# Sheet2.net
KiCad netlist of a schematic drawn in Altium Designer
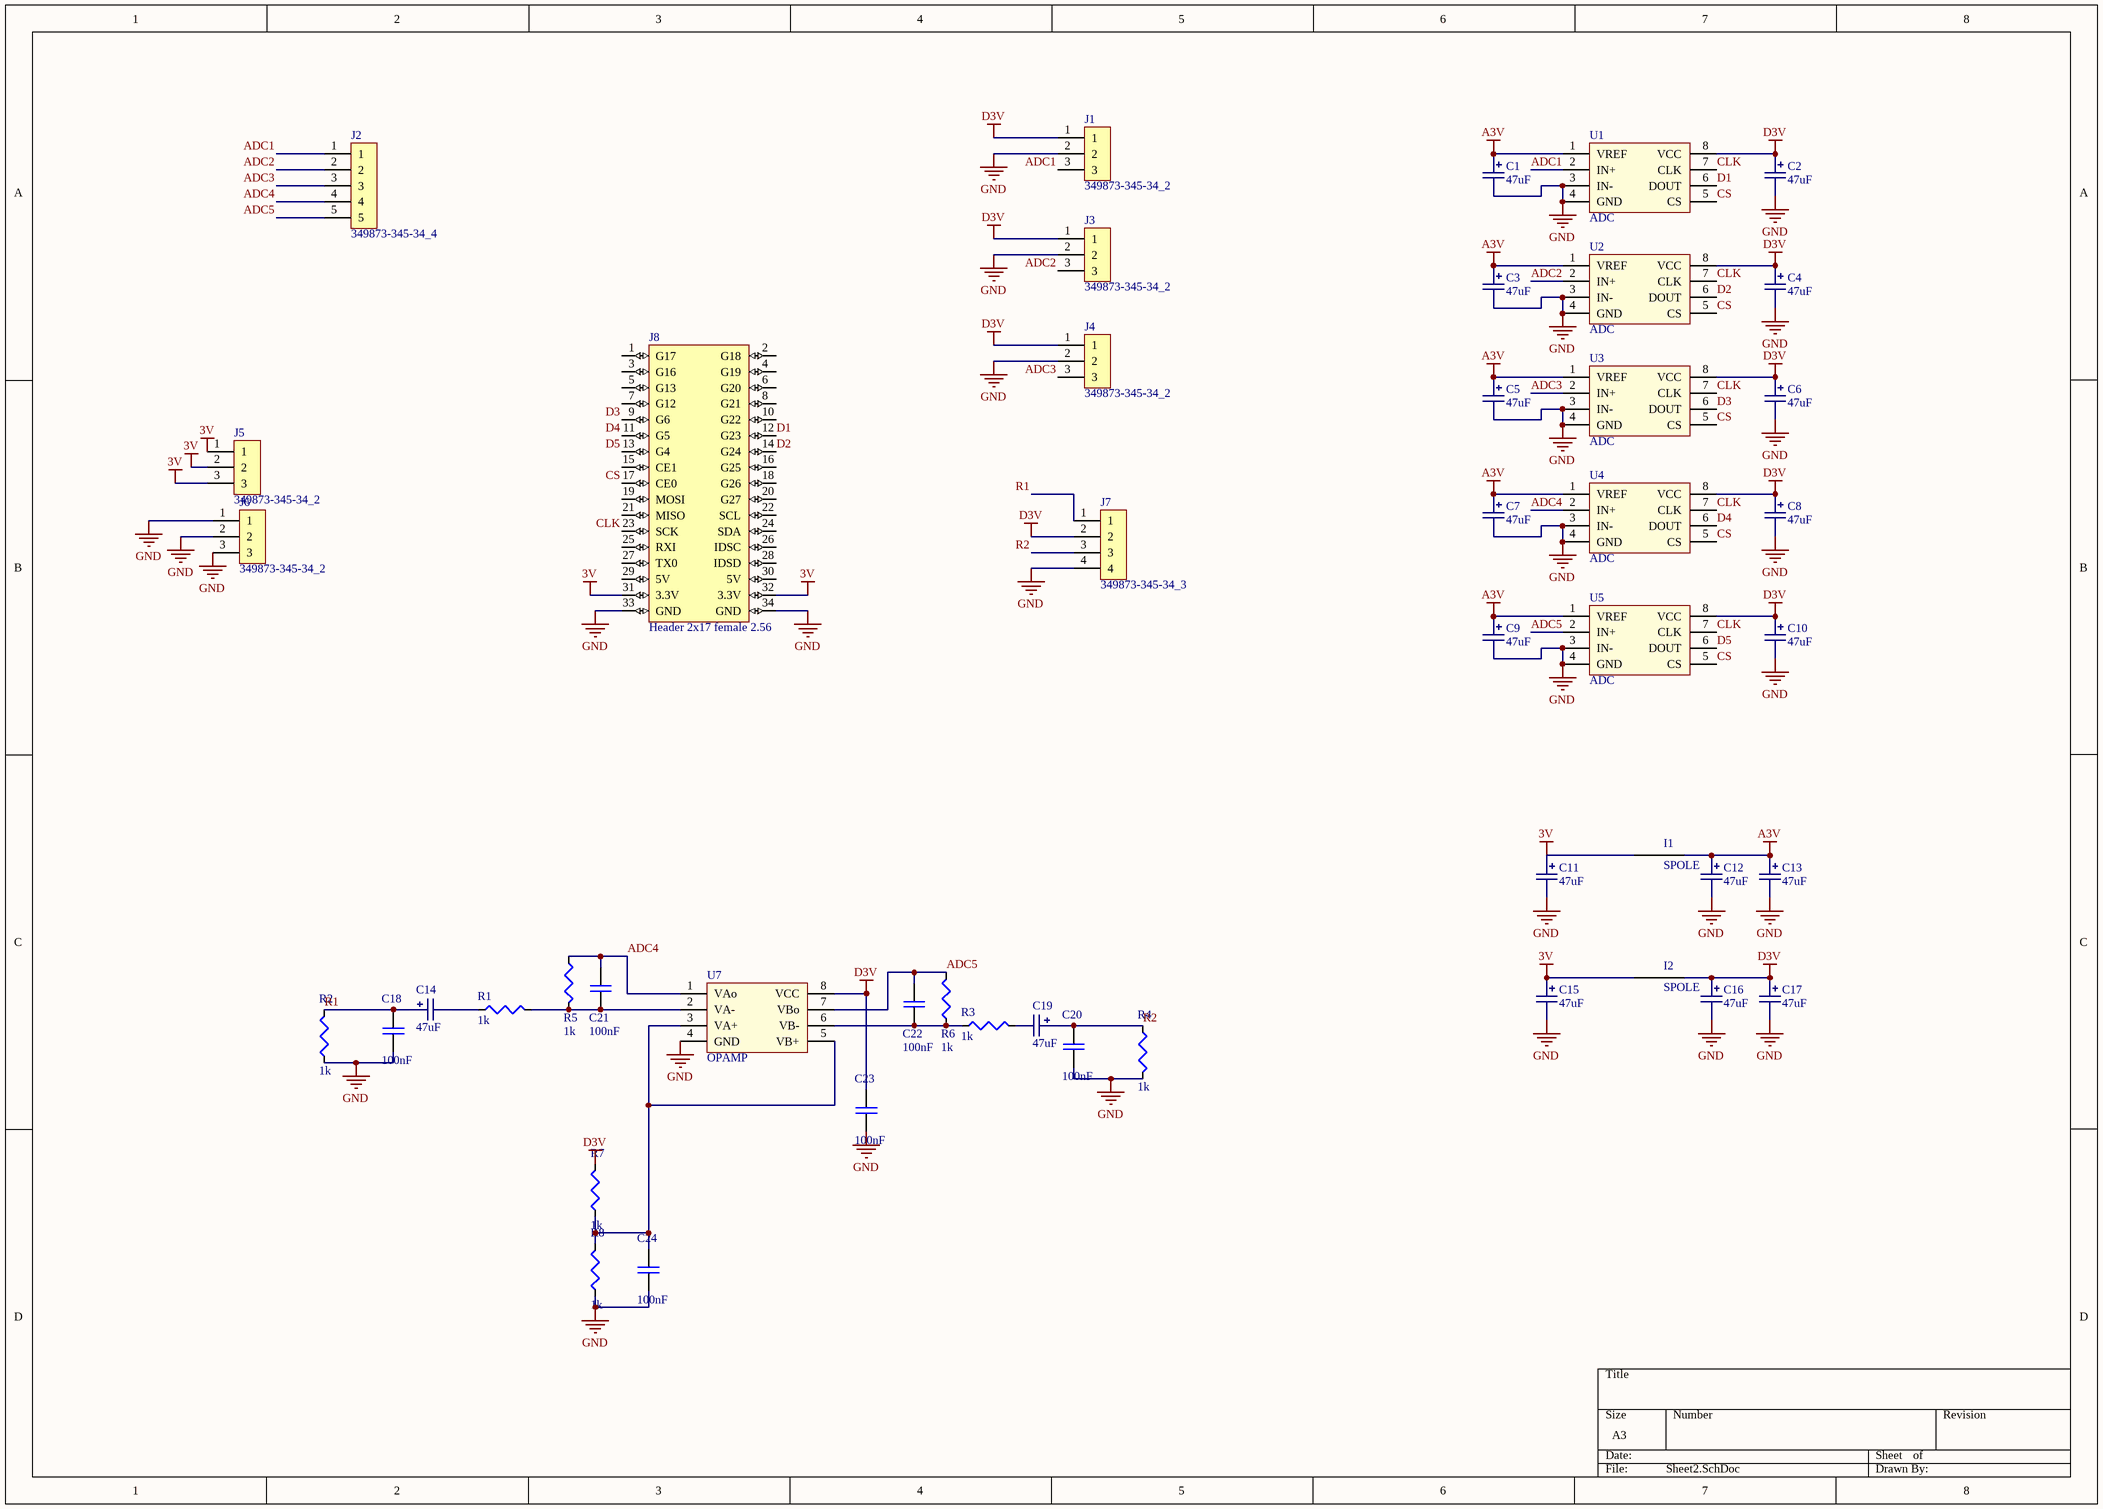
[diagram p0: Sheet2.SchDoc]

(export (version "E")
  (design (tool "Eeschema 10.0.6"))
  (components
    (comp (ref "C1")
      (value "47uF")
      (footprint "CAPPR20D05H11")
      (description "25V, Elektrolytt")
      (libsource (lib "OVLib_64") (part "POLCAP"))
    )
    (comp (ref "C2")
      (value "47uF")
      (footprint "CAPPR20D05H11")
      (description "25V, Elektrolytt")
      (libsource (lib "OVLib_64") (part "POLCAP"))
    )
    (comp (ref "C3")
      (value "47uF")
      (footprint "CAPPR20D05H11")
      (description "25V, Elektrolytt")
      (libsource (lib "OVLib_64") (part "POLCAP"))
    )
    (comp (ref "C4")
      (value "47uF")
      (footprint "CAPPR20D05H11")
      (description "25V, Elektrolytt")
      (libsource (lib "OVLib_64") (part "POLCAP"))
    )
    (comp (ref "C5")
      (value "47uF")
      (footprint "CAPPR20D05H11")
      (description "25V, Elektrolytt")
      (libsource (lib "OVLib_64") (part "POLCAP"))
    )
    (comp (ref "C6")
      (value "47uF")
      (footprint "CAPPR20D05H11")
      (description "25V, Elektrolytt")
      (libsource (lib "OVLib_64") (part "POLCAP"))
    )
    (comp (ref "C7")
      (value "47uF")
      (footprint "CAPPR20D05H11")
      (description "25V, Elektrolytt")
      (libsource (lib "OVLib_64") (part "POLCAP"))
    )
    (comp (ref "C8")
      (value "47uF")
      (footprint "CAPPR20D05H11")
      (description "25V, Elektrolytt")
      (libsource (lib "OVLib_64") (part "POLCAP"))
    )
    (comp (ref "C9")
      (value "47uF")
      (footprint "CAPPR20D05H11")
      (description "25V, Elektrolytt")
      (libsource (lib "OVLib_64") (part "POLCAP"))
    )
    (comp (ref "C10")
      (value "47uF")
      (footprint "CAPPR20D05H11")
      (description "25V, Elektrolytt")
      (libsource (lib "OVLib_64") (part "POLCAP"))
    )
    (comp (ref "C11")
      (value "47uF")
      (footprint "CAPPR20D05H11")
      (description "25V, Elektrolytt")
      (libsource (lib "OVLib_64") (part "POLCAP"))
    )
    (comp (ref "C12")
      (value "47uF")
      (footprint "CAPPR20D05H11")
      (description "25V, Elektrolytt")
      (libsource (lib "OVLib_64") (part "POLCAP"))
    )
    (comp (ref "C13")
      (value "47uF")
      (footprint "CAPPR20D05H11")
      (description "25V, Elektrolytt")
      (libsource (lib "OVLib_64") (part "POLCAP"))
    )
    (comp (ref "C14")
      (value "47uF")
      (footprint "CAPPR20D05H11")
      (description "25V, Elektrolytt")
      (libsource (lib "OVLib_64") (part "POLCAP"))
    )
    (comp (ref "C15")
      (value "47uF")
      (footprint "CAPPR20D05H11")
      (description "25V, Elektrolytt")
      (libsource (lib "OVLib_64") (part "POLCAP"))
    )
    (comp (ref "C16")
      (value "47uF")
      (footprint "CAPPR20D05H11")
      (description "25V, Elektrolytt")
      (libsource (lib "OVLib_64") (part "POLCAP"))
    )
    (comp (ref "C17")
      (value "47uF")
      (footprint "CAPPR20D05H11")
      (description "25V, Elektrolytt")
      (libsource (lib "OVLib_64") (part "POLCAP"))
    )
    (comp (ref "C18")
      (value "100nF")
      (footprint "C0805")
      (description "C0805")
      (fields (field (name "Comment") "08053C105KAT2A"))
      (libsource (lib "Passive components") (part "08053C105KAT2A"))
    )
    (comp (ref "C19")
      (value "47uF")
      (footprint "CAPPR20D05H11")
      (description "25V, Elektrolytt")
      (libsource (lib "OVLib_64") (part "POLCAP"))
    )
    (comp (ref "C20")
      (value "100nF")
      (footprint "C0805")
      (description "C0805")
      (fields (field (name "Comment") "08053C105KAT2A"))
      (libsource (lib "Passive components") (part "08053C105KAT2A"))
    )
    (comp (ref "C21")
      (value "100nF")
      (footprint "C0805")
      (description "C0805")
      (fields (field (name "Comment") "08053C105KAT2A"))
      (libsource (lib "Passive components") (part "08053C105KAT2A"))
    )
    (comp (ref "C22")
      (value "100nF")
      (footprint "C0805")
      (description "C0805")
      (fields (field (name "Comment") "08053C105KAT2A"))
      (libsource (lib "Passive components") (part "08053C105KAT2A"))
    )
    (comp (ref "C23")
      (value "100nF")
      (footprint "C0805")
      (description "C0805")
      (fields (field (name "Comment") "08053C105KAT2A"))
      (libsource (lib "Passive components") (part "08053C105KAT2A"))
    )
    (comp (ref "C24")
      (value "100nF")
      (footprint "C0805")
      (description "C0805")
      (fields (field (name "Comment") "08053C105KAT2A"))
      (libsource (lib "Passive components") (part "08053C105KAT2A"))
    )
    (comp (ref "I1")
      (value "SPOLE")
      (footprint "Microcontrollers:PCBComponent_1")
      (libsource (lib "Passive components") (part "SPOLE"))
    )
    (comp (ref "I2")
      (value "SPOLE")
      (footprint "Microcontrollers:PCBComponent_1")
      (libsource (lib "Passive components") (part "SPOLE"))
    )
    (comp (ref "J1")
      (value "349873-345-34_2")
      (footprint "Header 1x3 male")
      (description "Header 1x3 male 2.54mm")
      (libsource (lib "Connectors") (part "349873-345-34_2"))
    )
    (comp (ref "J2")
      (value "349873-345-34_4")
      (footprint "Header 1x5 male")
      (description "Header 1x5 male 2.54mm")
      (libsource (lib "Connectors") (part "349873-345-34_4"))
    )
    (comp (ref "J3")
      (value "349873-345-34_2")
      (footprint "Header 1x3 male")
      (description "Header 1x3 male 2.54mm")
      (libsource (lib "Connectors") (part "349873-345-34_2"))
    )
    (comp (ref "J4")
      (value "349873-345-34_2")
      (footprint "Header 1x3 male")
      (description "Header 1x3 male 2.54mm")
      (libsource (lib "Connectors") (part "349873-345-34_2"))
    )
    (comp (ref "J5")
      (value "349873-345-34_2")
      (footprint "Header 1x3 male")
      (description "Header 1x3 male 2.54mm")
      (libsource (lib "Connectors") (part "349873-345-34_2"))
    )
    (comp (ref "J6")
      (value "349873-345-34_2")
      (footprint "Header 1x3 male")
      (description "Header 1x3 male 2.54mm")
      (libsource (lib "Connectors") (part "349873-345-34_2"))
    )
    (comp (ref "J7")
      (value "349873-345-34_3")
      (footprint "Header 1x4 male")
      (description "Header 1x4 male 2.54mm")
      (libsource (lib "Connectors") (part "349873-345-34_3"))
    )
    (comp (ref "J8")
      (value "Header 2x17 female 2.56")
      (footprint "Header 2x17 female 2.56")
      (libsource (lib "Connectors") (part "Header 2x17 female 2.56"))
    )
    (comp (ref "R1")
      (value "1k")
      (footprint "R0805")
      (description "R0805")
      (fields (field (name "Comment") "CRCW08050000Z0EA"))
      (libsource (lib "Passive components") (part "CRCW08050000Z0EA"))
    )
    (comp (ref "R2")
      (value "1k")
      (footprint "R0805")
      (description "R0805")
      (fields (field (name "Comment") "CRCW08050000Z0EA"))
      (libsource (lib "Passive components") (part "CRCW08050000Z0EA"))
    )
    (comp (ref "R3")
      (value "1k")
      (footprint "R0805")
      (description "R0805")
      (fields (field (name "Comment") "CRCW08050000Z0EA"))
      (libsource (lib "Passive components") (part "CRCW08050000Z0EA"))
    )
    (comp (ref "R4")
      (value "1k")
      (footprint "R0805")
      (description "R0805")
      (fields (field (name "Comment") "CRCW08050000Z0EA"))
      (libsource (lib "Passive components") (part "CRCW08050000Z0EA"))
    )
    (comp (ref "R5")
      (value "1k")
      (footprint "R0805")
      (description "R0805")
      (fields (field (name "Comment") "CRCW08050000Z0EA"))
      (libsource (lib "Passive components") (part "CRCW08050000Z0EA"))
    )
    (comp (ref "R6")
      (value "1k")
      (footprint "R0805")
      (description "R0805")
      (fields (field (name "Comment") "CRCW08050000Z0EA"))
      (libsource (lib "Passive components") (part "CRCW08050000Z0EA"))
    )
    (comp (ref "R7")
      (value "1k")
      (footprint "R0805")
      (description "R0805")
      (fields (field (name "Comment") "CRCW08050000Z0EA"))
      (libsource (lib "Passive components") (part "CRCW08050000Z0EA"))
    )
    (comp (ref "R8")
      (value "1k")
      (footprint "R0805")
      (description "R0805")
      (fields (field (name "Comment") "CRCW08050000Z0EA"))
      (libsource (lib "Passive components") (part "CRCW08050000Z0EA"))
    )
    (comp (ref "U1") (value "ADC") (footprint "SOKKEL8") (libsource (lib "Microcontrollers") (part "ADC")))
    (comp (ref "U2") (value "ADC") (footprint "SOKKEL8") (libsource (lib "Microcontrollers") (part "ADC")))
    (comp (ref "U3") (value "ADC") (footprint "SOKKEL8") (libsource (lib "Microcontrollers") (part "ADC")))
    (comp (ref "U4") (value "ADC") (footprint "SOKKEL8") (libsource (lib "Microcontrollers") (part "ADC")))
    (comp (ref "U5") (value "ADC") (footprint "SOKKEL8") (libsource (lib "Microcontrollers") (part "ADC")))
    (comp (ref "U7")
      (value "OPAMP")
      (footprint "Microcontrollers:SOKKEL8")
      (libsource (lib "Microcontrollers") (part "OPAMP"))
    )
  )
  (nets
    (net (code "1") (name "/ADC1") (class "Default")
      (node (ref "J1") (pin "3") (pinfunction "3_3") (pintype "passive"))
      (node (ref "J2") (pin "1") (pinfunction "1_1") (pintype "passive"))
      (node (ref "U1") (pin "2") (pinfunction "IN+_2") (pintype "power_in"))
    )
    (net (code "2") (name "/ADC2") (class "Default")
      (node (ref "J2") (pin "2") (pinfunction "2_2") (pintype "passive"))
      (node (ref "J3") (pin "3") (pinfunction "3_3") (pintype "passive"))
      (node (ref "U2") (pin "2") (pinfunction "IN+_2") (pintype "power_in"))
    )
    (net (code "3") (name "/ADC3") (class "Default")
      (node (ref "J2") (pin "3") (pinfunction "3_3") (pintype "passive"))
      (node (ref "J4") (pin "3") (pinfunction "3_3") (pintype "passive"))
      (node (ref "U3") (pin "2") (pinfunction "IN+_2") (pintype "power_in"))
    )
    (net (code "4") (name "/ADC4") (class "Default")
      (node (ref "C21") (pin "1") (pinfunction "1_1") (pintype "passive"))
      (node (ref "J2") (pin "4") (pinfunction "4_4") (pintype "passive"))
      (node (ref "R5") (pin "1") (pinfunction "1_1") (pintype "passive"))
      (node (ref "U4") (pin "2") (pinfunction "IN+_2") (pintype "power_in"))
      (node (ref "U7") (pin "1") (pinfunction "VAo_1") (pintype "power_in"))
    )
    (net (code "5") (name "/ADC5") (class "Default")
      (node (ref "C22") (pin "1") (pinfunction "1_1") (pintype "passive"))
      (node (ref "J2") (pin "5") (pinfunction "5_5") (pintype "passive"))
      (node (ref "R6") (pin "1") (pinfunction "1_1") (pintype "passive"))
      (node (ref "U5") (pin "2") (pinfunction "IN+_2") (pintype "power_in"))
      (node (ref "U7") (pin "7") (pinfunction "VBo_7") (pintype "power_in"))
    )
    (net (code "6") (name "/CLK") (class "Default")
      (node (ref "J8") (pin "23") (pinfunction "SCK_23") (pintype "bidirectional"))
      (node (ref "U1") (pin "7") (pinfunction "CLK_7") (pintype "power_in"))
      (node (ref "U2") (pin "7") (pinfunction "CLK_7") (pintype "power_in"))
      (node (ref "U3") (pin "7") (pinfunction "CLK_7") (pintype "power_in"))
      (node (ref "U4") (pin "7") (pinfunction "CLK_7") (pintype "power_in"))
      (node (ref "U5") (pin "7") (pinfunction "CLK_7") (pintype "power_in"))
    )
    (net (code "7") (name "/CS") (class "Default")
      (node (ref "J8") (pin "17") (pinfunction "CE0_17") (pintype "bidirectional"))
      (node (ref "U1") (pin "5") (pinfunction "CS_5") (pintype "power_in"))
      (node (ref "U2") (pin "5") (pinfunction "CS_5") (pintype "power_in"))
      (node (ref "U3") (pin "5") (pinfunction "CS_5") (pintype "power_in"))
      (node (ref "U4") (pin "5") (pinfunction "CS_5") (pintype "power_in"))
      (node (ref "U5") (pin "5") (pinfunction "CS_5") (pintype "power_in"))
    )
    (net (code "8") (name "/D1") (class "Default")
      (node (ref "J8") (pin "12") (pinfunction "G23_12") (pintype "bidirectional"))
      (node (ref "U1") (pin "6") (pinfunction "DOUT_6") (pintype "power_in"))
    )
    (net (code "9") (name "/D2") (class "Default")
      (node (ref "J8") (pin "14") (pinfunction "G24_14") (pintype "bidirectional"))
      (node (ref "U2") (pin "6") (pinfunction "DOUT_6") (pintype "power_in"))
    )
    (net (code "10") (name "/D3") (class "Default")
      (node (ref "J8") (pin "9") (pinfunction "G6_9") (pintype "bidirectional"))
      (node (ref "U3") (pin "6") (pinfunction "DOUT_6") (pintype "power_in"))
    )
    (net (code "11") (name "/D4") (class "Default")
      (node (ref "J8") (pin "11") (pinfunction "G5_11") (pintype "bidirectional"))
      (node (ref "U4") (pin "6") (pinfunction "DOUT_6") (pintype "power_in"))
    )
    (net (code "12") (name "/D5") (class "Default")
      (node (ref "J8") (pin "13") (pinfunction "G4_13") (pintype "bidirectional"))
      (node (ref "U5") (pin "6") (pinfunction "DOUT_6") (pintype "power_in"))
    )
    (net (code "13") (name "/R1") (class "Default")
      (node (ref "C14") (pin "2") (pinfunction "2_2") (pintype "passive"))
      (node (ref "C18") (pin "2") (pinfunction "2_2") (pintype "passive"))
      (node (ref "J7") (pin "1") (pinfunction "1_1") (pintype "passive"))
      (node (ref "R2") (pin "2") (pinfunction "2_2") (pintype "passive"))
    )
    (net (code "14") (name "/R2") (class "Default")
      (node (ref "C19") (pin "2") (pinfunction "2_2") (pintype "passive"))
      (node (ref "C20") (pin "2") (pinfunction "2_2") (pintype "passive"))
      (node (ref "J7") (pin "3") (pinfunction "3_3") (pintype "passive"))
      (node (ref "R4") (pin "2") (pinfunction "2_2") (pintype "passive"))
    )
    (net (code "15") (name "3V") (class "Default")
      (node (ref "C11") (pin "2") (pinfunction "2_2") (pintype "passive"))
      (node (ref "C15") (pin "2") (pinfunction "2_2") (pintype "passive"))
      (node (ref "I1") (pin "1") (pinfunction "1_1") (pintype "power_in"))
      (node (ref "I2") (pin "1") (pinfunction "1_1") (pintype "power_in"))
      (node (ref "J5") (pin "1") (pinfunction "1_1") (pintype "passive"))
      (node (ref "J5") (pin "2") (pinfunction "2_2") (pintype "passive"))
      (node (ref "J5") (pin "3") (pinfunction "3_3") (pintype "passive"))
      (node (ref "J8") (pin "31") (pinfunction "3.3V_31") (pintype "bidirectional"))
      (node (ref "J8") (pin "32") (pinfunction "3.3V_32") (pintype "bidirectional"))
    )
    (net (code "16") (name "A3V") (class "Default")
      (node (ref "C1") (pin "2") (pinfunction "2_2") (pintype "passive"))
      (node (ref "C12") (pin "2") (pinfunction "2_2") (pintype "passive"))
      (node (ref "C13") (pin "2") (pinfunction "2_2") (pintype "passive"))
      (node (ref "C3") (pin "2") (pinfunction "2_2") (pintype "passive"))
      (node (ref "C5") (pin "2") (pinfunction "2_2") (pintype "passive"))
      (node (ref "C7") (pin "2") (pinfunction "2_2") (pintype "passive"))
      (node (ref "C9") (pin "2") (pinfunction "2_2") (pintype "passive"))
      (node (ref "I1") (pin "2") (pinfunction "2_2") (pintype "power_in"))
      (node (ref "U1") (pin "1") (pinfunction "VREF_1") (pintype "power_in"))
      (node (ref "U2") (pin "1") (pinfunction "VREF_1") (pintype "power_in"))
      (node (ref "U3") (pin "1") (pinfunction "VREF_1") (pintype "power_in"))
      (node (ref "U4") (pin "1") (pinfunction "VREF_1") (pintype "power_in"))
      (node (ref "U5") (pin "1") (pinfunction "VREF_1") (pintype "power_in"))
    )
    (net (code "17") (name "D3V") (class "Default")
      (node (ref "C10") (pin "2") (pinfunction "2_2") (pintype "passive"))
      (node (ref "C16") (pin "2") (pinfunction "2_2") (pintype "passive"))
      (node (ref "C17") (pin "2") (pinfunction "2_2") (pintype "passive"))
      (node (ref "C2") (pin "2") (pinfunction "2_2") (pintype "passive"))
      (node (ref "C23") (pin "2") (pinfunction "2_2") (pintype "passive"))
      (node (ref "C4") (pin "2") (pinfunction "2_2") (pintype "passive"))
      (node (ref "C6") (pin "2") (pinfunction "2_2") (pintype "passive"))
      (node (ref "C8") (pin "2") (pinfunction "2_2") (pintype "passive"))
      (node (ref "I2") (pin "2") (pinfunction "2_2") (pintype "power_in"))
      (node (ref "J1") (pin "1") (pinfunction "1_1") (pintype "passive"))
      (node (ref "J3") (pin "1") (pinfunction "1_1") (pintype "passive"))
      (node (ref "J4") (pin "1") (pinfunction "1_1") (pintype "passive"))
      (node (ref "J7") (pin "2") (pinfunction "2_2") (pintype "passive"))
      (node (ref "R7") (pin "2") (pinfunction "2_2") (pintype "passive"))
      (node (ref "U1") (pin "8") (pinfunction "VCC_8") (pintype "power_in"))
      (node (ref "U2") (pin "8") (pinfunction "VCC_8") (pintype "power_in"))
      (node (ref "U3") (pin "8") (pinfunction "VCC_8") (pintype "power_in"))
      (node (ref "U4") (pin "8") (pinfunction "VCC_8") (pintype "power_in"))
      (node (ref "U5") (pin "8") (pinfunction "VCC_8") (pintype "power_in"))
      (node (ref "U7") (pin "8") (pinfunction "VCC_8") (pintype "power_in"))
    )
    (net (code "18") (name "GND") (class "Default")
      (node (ref "C1") (pin "1") (pinfunction "1_1") (pintype "passive"))
      (node (ref "C10") (pin "1") (pinfunction "1_1") (pintype "passive"))
      (node (ref "C11") (pin "1") (pinfunction "1_1") (pintype "passive"))
      (node (ref "C12") (pin "1") (pinfunction "1_1") (pintype "passive"))
      (node (ref "C13") (pin "1") (pinfunction "1_1") (pintype "passive"))
      (node (ref "C15") (pin "1") (pinfunction "1_1") (pintype "passive"))
      (node (ref "C16") (pin "1") (pinfunction "1_1") (pintype "passive"))
      (node (ref "C17") (pin "1") (pinfunction "1_1") (pintype "passive"))
      (node (ref "C18") (pin "1") (pinfunction "1_1") (pintype "passive"))
      (node (ref "C2") (pin "1") (pinfunction "1_1") (pintype "passive"))
      (node (ref "C20") (pin "1") (pinfunction "1_1") (pintype "passive"))
      (node (ref "C23") (pin "1") (pinfunction "1_1") (pintype "passive"))
      (node (ref "C24") (pin "1") (pinfunction "1_1") (pintype "passive"))
      (node (ref "C3") (pin "1") (pinfunction "1_1") (pintype "passive"))
      (node (ref "C4") (pin "1") (pinfunction "1_1") (pintype "passive"))
      (node (ref "C5") (pin "1") (pinfunction "1_1") (pintype "passive"))
      (node (ref "C6") (pin "1") (pinfunction "1_1") (pintype "passive"))
      (node (ref "C7") (pin "1") (pinfunction "1_1") (pintype "passive"))
      (node (ref "C8") (pin "1") (pinfunction "1_1") (pintype "passive"))
      (node (ref "C9") (pin "1") (pinfunction "1_1") (pintype "passive"))
      (node (ref "J1") (pin "2") (pinfunction "2_2") (pintype "passive"))
      (node (ref "J3") (pin "2") (pinfunction "2_2") (pintype "passive"))
      (node (ref "J4") (pin "2") (pinfunction "2_2") (pintype "passive"))
      (node (ref "J6") (pin "1") (pinfunction "1_1") (pintype "passive"))
      (node (ref "J6") (pin "2") (pinfunction "2_2") (pintype "passive"))
      (node (ref "J6") (pin "3") (pinfunction "3_3") (pintype "passive"))
      (node (ref "J7") (pin "4") (pinfunction "4_4") (pintype "passive"))
      (node (ref "J8") (pin "33") (pinfunction "GND_33") (pintype "bidirectional"))
      (node (ref "J8") (pin "34") (pinfunction "GND_34") (pintype "bidirectional"))
      (node (ref "R2") (pin "1") (pinfunction "1_1") (pintype "passive"))
      (node (ref "R4") (pin "1") (pinfunction "1_1") (pintype "passive"))
      (node (ref "R8") (pin "1") (pinfunction "1_1") (pintype "passive"))
      (node (ref "U1") (pin "3") (pinfunction "IN-_3") (pintype "power_in"))
      (node (ref "U1") (pin "4") (pinfunction "GND_4") (pintype "power_in"))
      (node (ref "U2") (pin "3") (pinfunction "IN-_3") (pintype "power_in"))
      (node (ref "U2") (pin "4") (pinfunction "GND_4") (pintype "power_in"))
      (node (ref "U3") (pin "3") (pinfunction "IN-_3") (pintype "power_in"))
      (node (ref "U3") (pin "4") (pinfunction "GND_4") (pintype "power_in"))
      (node (ref "U4") (pin "3") (pinfunction "IN-_3") (pintype "power_in"))
      (node (ref "U4") (pin "4") (pinfunction "GND_4") (pintype "power_in"))
      (node (ref "U5") (pin "3") (pinfunction "IN-_3") (pintype "power_in"))
      (node (ref "U5") (pin "4") (pinfunction "GND_4") (pintype "power_in"))
      (node (ref "U7") (pin "4") (pinfunction "GND_4") (pintype "power_in"))
    )
    (net (code "19") (name "Net-(C14-Pad1)") (class "Default")
      (node (ref "C14") (pin "1") (pinfunction "1_1") (pintype "passive"))
      (node (ref "R1") (pin "2") (pinfunction "2_2") (pintype "passive"))
    )
    (net (code "20") (name "Net-(C19-Pad1)") (class "Default")
      (node (ref "C19") (pin "1") (pinfunction "1_1") (pintype "passive"))
      (node (ref "R3") (pin "1") (pinfunction "1_1") (pintype "passive"))
    )
    (net (code "21") (name "Net-(U7-VA+)") (class "Default")
      (node (ref "C24") (pin "2") (pinfunction "2_2") (pintype "passive"))
      (node (ref "R7") (pin "1") (pinfunction "1_1") (pintype "passive"))
      (node (ref "R8") (pin "2") (pinfunction "2_2") (pintype "passive"))
      (node (ref "U7") (pin "3") (pinfunction "VA+_3") (pintype "power_in"))
      (node (ref "U7") (pin "5") (pinfunction "VB+_5") (pintype "power_in"))
    )
    (net (code "22") (name "Net-(U7-VA-)") (class "Default")
      (node (ref "C21") (pin "2") (pinfunction "2_2") (pintype "passive"))
      (node (ref "R1") (pin "1") (pinfunction "1_1") (pintype "passive"))
      (node (ref "R5") (pin "2") (pinfunction "2_2") (pintype "passive"))
      (node (ref "U7") (pin "2") (pinfunction "VA-_2") (pintype "power_in"))
    )
    (net (code "23") (name "Net-(U7-VB-)") (class "Default")
      (node (ref "C22") (pin "2") (pinfunction "2_2") (pintype "passive"))
      (node (ref "R3") (pin "2") (pinfunction "2_2") (pintype "passive"))
      (node (ref "R6") (pin "2") (pinfunction "2_2") (pintype "passive"))
      (node (ref "U7") (pin "6") (pinfunction "VB-_6") (pintype "power_in"))
    )
    (net (code "24") (name "unconnected-(J8-5V-Pad29)") (class "Default")
      (node (ref "J8") (pin "29") (pinfunction "5V_29") (pintype "bidirectional"))
    )
    (net (code "25") (name "unconnected-(J8-5V-Pad30)") (class "Default")
      (node (ref "J8") (pin "30") (pinfunction "5V_30") (pintype "bidirectional"))
    )
    (net (code "26") (name "unconnected-(J8-CE1-Pad15)") (class "Default")
      (node (ref "J8") (pin "15") (pinfunction "CE1_15") (pintype "bidirectional"))
    )
    (net (code "27") (name "unconnected-(J8-G12-Pad7)") (class "Default")
      (node (ref "J8") (pin "7") (pinfunction "G12_7") (pintype "bidirectional"))
    )
    (net (code "28") (name "unconnected-(J8-G13-Pad5)") (class "Default")
      (node (ref "J8") (pin "5") (pinfunction "G13_5") (pintype "bidirectional"))
    )
    (net (code "29") (name "unconnected-(J8-G16-Pad3)") (class "Default")
      (node (ref "J8") (pin "3") (pinfunction "G16_3") (pintype "bidirectional"))
    )
    (net (code "30") (name "unconnected-(J8-G17-Pad1)") (class "Default")
      (node (ref "J8") (pin "1") (pinfunction "G17_1") (pintype "bidirectional"))
    )
    (net (code "31") (name "unconnected-(J8-G18-Pad2)") (class "Default")
      (node (ref "J8") (pin "2") (pinfunction "G18_2") (pintype "bidirectional"))
    )
    (net (code "32") (name "unconnected-(J8-G19-Pad4)") (class "Default")
      (node (ref "J8") (pin "4") (pinfunction "G19_4") (pintype "bidirectional"))
    )
    (net (code "33") (name "unconnected-(J8-G20-Pad6)") (class "Default")
      (node (ref "J8") (pin "6") (pinfunction "G20_6") (pintype "bidirectional"))
    )
    (net (code "34") (name "unconnected-(J8-G21-Pad8)") (class "Default")
      (node (ref "J8") (pin "8") (pinfunction "G21_8") (pintype "bidirectional"))
    )
    (net (code "35") (name "unconnected-(J8-G22-Pad10)") (class "Default")
      (node (ref "J8") (pin "10") (pinfunction "G22_10") (pintype "bidirectional"))
    )
    (net (code "36") (name "unconnected-(J8-G25-Pad16)") (class "Default")
      (node (ref "J8") (pin "16") (pinfunction "G25_16") (pintype "bidirectional"))
    )
    (net (code "37") (name "unconnected-(J8-G26-Pad18)") (class "Default")
      (node (ref "J8") (pin "18") (pinfunction "G26_18") (pintype "bidirectional"))
    )
    (net (code "38") (name "unconnected-(J8-G27-Pad20)") (class "Default")
      (node (ref "J8") (pin "20") (pinfunction "G27_20") (pintype "bidirectional"))
    )
    (net (code "39") (name "unconnected-(J8-IDSC-Pad26)") (class "Default")
      (node (ref "J8") (pin "26") (pinfunction "IDSC_26") (pintype "bidirectional"))
    )
    (net (code "40") (name "unconnected-(J8-IDSD-Pad28)") (class "Default")
      (node (ref "J8") (pin "28") (pinfunction "IDSD_28") (pintype "bidirectional"))
    )
    (net (code "41") (name "unconnected-(J8-MISO-Pad21)") (class "Default")
      (node (ref "J8") (pin "21") (pinfunction "MISO_21") (pintype "bidirectional"))
    )
    (net (code "42") (name "unconnected-(J8-MOSI-Pad19)") (class "Default")
      (node (ref "J8") (pin "19") (pinfunction "MOSI_19") (pintype "bidirectional"))
    )
    (net (code "43") (name "unconnected-(J8-RXI-Pad25)") (class "Default")
      (node (ref "J8") (pin "25") (pinfunction "RXI_25") (pintype "bidirectional"))
    )
    (net (code "44") (name "unconnected-(J8-SCL-Pad22)") (class "Default")
      (node (ref "J8") (pin "22") (pinfunction "SCL_22") (pintype "bidirectional"))
    )
    (net (code "45") (name "unconnected-(J8-SDA-Pad24)") (class "Default")
      (node (ref "J8") (pin "24") (pinfunction "SDA_24") (pintype "bidirectional"))
    )
    (net (code "46") (name "unconnected-(J8-TX0-Pad27)") (class "Default")
      (node (ref "J8") (pin "27") (pinfunction "TX0_27") (pintype "bidirectional"))
    )
  )
)
